# SuperAli.net
KiCad netlist of a schematic drawn in EAGLE
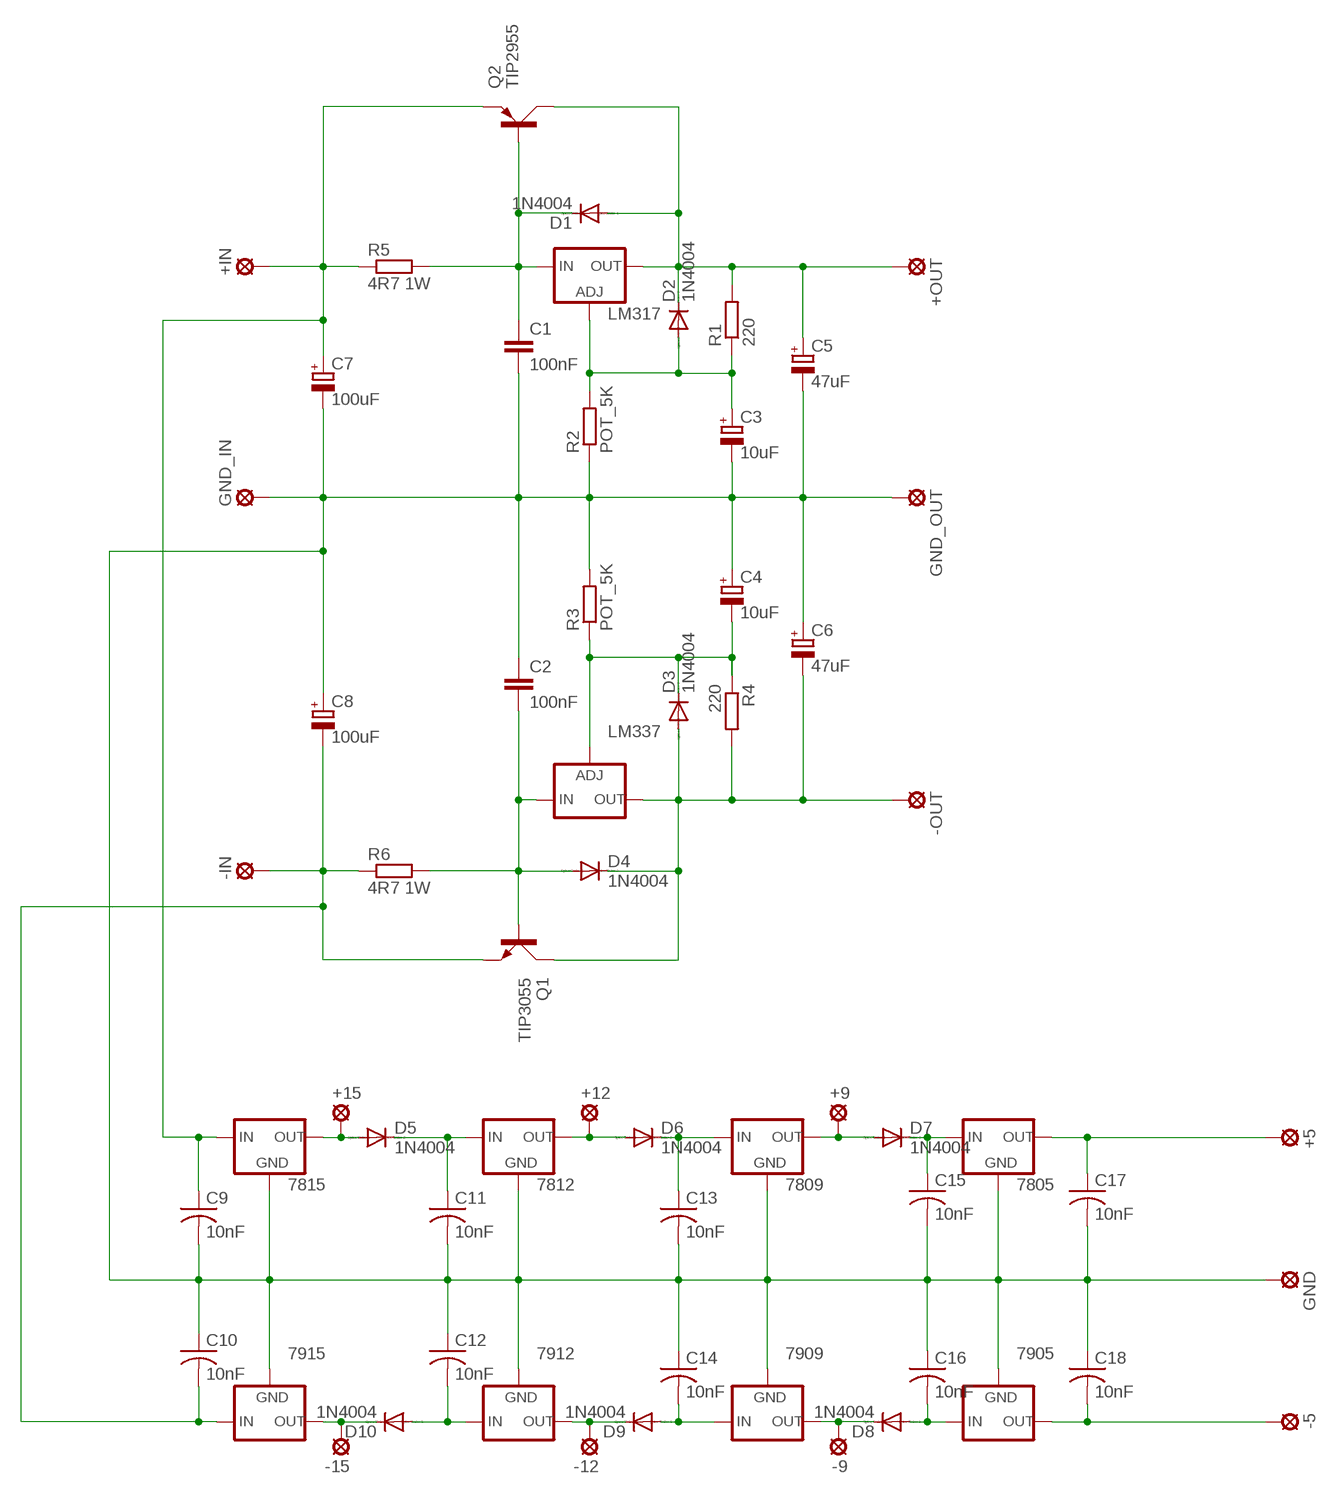
[diagram p0: schematic, sheet 1]

(export (version "E")
  (design (tool "Eeschema 10.0.6"))
  (components
    (comp (ref "+5")
      (value "LSP10")
      (footprint "eagle-import:LSP10")
      (libsource (lib "eagle-import") (part "LSP10"))
    )
    (comp (ref "+9")
      (value "LSP10")
      (footprint "eagle-import:LSP10")
      (libsource (lib "eagle-import") (part "LSP10"))
    )
    (comp (ref "+12")
      (value "LSP10")
      (footprint "eagle-import:LSP10")
      (libsource (lib "eagle-import") (part "LSP10"))
    )
    (comp (ref "+15")
      (value "LSP10")
      (footprint "eagle-import:LSP10")
      (libsource (lib "eagle-import") (part "LSP10"))
    )
    (comp (ref "+IN")
      (value "LSP13")
      (footprint "eagle-import:LSP13")
      (libsource (lib "eagle-import") (part "LSP13"))
    )
    (comp (ref "+OUT")
      (value "LSP13")
      (footprint "eagle-import:LSP13")
      (libsource (lib "eagle-import") (part "LSP13"))
    )
    (comp (ref "-5")
      (value "LSP10")
      (footprint "eagle-import:LSP10")
      (libsource (lib "eagle-import") (part "LSP10"))
    )
    (comp (ref "-9")
      (value "LSP10")
      (footprint "eagle-import:LSP10")
      (libsource (lib "eagle-import") (part "LSP10"))
    )
    (comp (ref "-12")
      (value "LSP10")
      (footprint "eagle-import:LSP10")
      (libsource (lib "eagle-import") (part "LSP10"))
    )
    (comp (ref "-15")
      (value "LSP10")
      (footprint "eagle-import:LSP10")
      (libsource (lib "eagle-import") (part "LSP10"))
    )
    (comp (ref "-IN")
      (value "LSP13")
      (footprint "eagle-import:LSP13")
      (libsource (lib "eagle-import") (part "LSP13"))
    )
    (comp (ref "-OUT")
      (value "LSP13")
      (footprint "eagle-import:LSP13")
      (libsource (lib "eagle-import") (part "LSP13"))
    )
    (comp (ref "7805")
      (value "78XXS")
      (footprint "eagle-import:78XXS")
      (libsource (lib "eagle-import") (part "78XXS"))
    )
    (comp (ref "7809")
      (value "78XXS")
      (footprint "eagle-import:78XXS")
      (libsource (lib "eagle-import") (part "78XXS"))
    )
    (comp (ref "7812")
      (value "78XXS")
      (footprint "eagle-import:78XXS")
      (libsource (lib "eagle-import") (part "78XXS"))
    )
    (comp (ref "7815")
      (value "78XXS")
      (footprint "eagle-import:78XXS")
      (libsource (lib "eagle-import") (part "78XXS"))
    )
    (comp (ref "7905")
      (value "79XXS")
      (footprint "eagle-import:79XXS")
      (libsource (lib "eagle-import") (part "79XXS"))
    )
    (comp (ref "7909")
      (value "79XXS")
      (footprint "eagle-import:79XXS")
      (libsource (lib "eagle-import") (part "79XXS"))
    )
    (comp (ref "7912")
      (value "79XXS")
      (footprint "eagle-import:79XXS")
      (libsource (lib "eagle-import") (part "79XXS"))
    )
    (comp (ref "7915")
      (value "79XXS")
      (footprint "eagle-import:79XXS")
      (libsource (lib "eagle-import") (part "79XXS"))
    )
    (comp (ref "C1")
      (value "100nF")
      (footprint "eagle-import:C025-040X050")
      (libsource (lib "eagle-import") (part "C-EU025-040X050"))
    )
    (comp (ref "C2")
      (value "100nF")
      (footprint "eagle-import:C025-040X050")
      (libsource (lib "eagle-import") (part "C-EU025-040X050"))
    )
    (comp (ref "C3")
      (value "10uF")
      (footprint "eagle-import:E2-5")
      (libsource (lib "eagle-import") (part "CPOL-EUE2-5"))
    )
    (comp (ref "C4")
      (value "10uF")
      (footprint "eagle-import:E2-5")
      (libsource (lib "eagle-import") (part "CPOL-EUE2-5"))
    )
    (comp (ref "C5")
      (value "47uF")
      (footprint "eagle-import:E3,5-10")
      (libsource (lib "eagle-import") (part "CPOL-EUE3.5-10"))
    )
    (comp (ref "C6")
      (value "47uF")
      (footprint "eagle-import:E3,5-10")
      (libsource (lib "eagle-import") (part "CPOL-EUE3.5-10"))
    )
    (comp (ref "C7")
      (value "100uF")
      (footprint "eagle-import:E7,5-16")
      (libsource (lib "eagle-import") (part "CPOL-EUE7.5-16"))
    )
    (comp (ref "C8")
      (value "100uF")
      (footprint "eagle-import:E7,5-16")
      (libsource (lib "eagle-import") (part "CPOL-EUE7.5-16"))
    )
    (comp (ref "C9")
      (value "10nF")
      (footprint "eagle-import:C025-025X050")
      (libsource (lib "eagle-import") (part "C-US025-025X050"))
    )
    (comp (ref "C10")
      (value "10nF")
      (footprint "eagle-import:C025-025X050")
      (libsource (lib "eagle-import") (part "C-US025-025X050"))
    )
    (comp (ref "C11")
      (value "10nF")
      (footprint "eagle-import:C025-025X050")
      (libsource (lib "eagle-import") (part "C-US025-025X050"))
    )
    (comp (ref "C12")
      (value "10nF")
      (footprint "eagle-import:C025-025X050")
      (libsource (lib "eagle-import") (part "C-US025-025X050"))
    )
    (comp (ref "C13")
      (value "10nF")
      (footprint "eagle-import:C025-025X050")
      (libsource (lib "eagle-import") (part "C-US025-025X050"))
    )
    (comp (ref "C14")
      (value "10nF")
      (footprint "eagle-import:C025-025X050")
      (libsource (lib "eagle-import") (part "C-US025-025X050"))
    )
    (comp (ref "C15")
      (value "10nF")
      (footprint "eagle-import:C025-025X050")
      (libsource (lib "eagle-import") (part "C-US025-025X050"))
    )
    (comp (ref "C16")
      (value "10nF")
      (footprint "eagle-import:C025-025X050")
      (libsource (lib "eagle-import") (part "C-US025-025X050"))
    )
    (comp (ref "C17")
      (value "10nF")
      (footprint "eagle-import:C025-025X050")
      (libsource (lib "eagle-import") (part "C-US025-025X050"))
    )
    (comp (ref "C18")
      (value "10nF")
      (footprint "eagle-import:C025-025X050")
      (libsource (lib "eagle-import") (part "C-US025-025X050"))
    )
    (comp (ref "D1")
      (value "1N4004")
      (footprint "eagle-import:DO41-10")
      (libsource (lib "eagle-import") (part "1N4004"))
    )
    (comp (ref "D2")
      (value "1N4004")
      (footprint "eagle-import:DO41-10")
      (libsource (lib "eagle-import") (part "1N4004"))
    )
    (comp (ref "D3")
      (value "1N4004")
      (footprint "eagle-import:DO41-10")
      (libsource (lib "eagle-import") (part "1N4004"))
    )
    (comp (ref "D4")
      (value "1N4004")
      (footprint "eagle-import:DO41-10")
      (libsource (lib "eagle-import") (part "1N4004"))
    )
    (comp (ref "D5")
      (value "1N4004")
      (footprint "eagle-import:DO41-10")
      (libsource (lib "eagle-import") (part "1N4004"))
    )
    (comp (ref "D6")
      (value "1N4004")
      (footprint "eagle-import:DO41-10")
      (libsource (lib "eagle-import") (part "1N4004"))
    )
    (comp (ref "D7")
      (value "1N4004")
      (footprint "eagle-import:DO41-10")
      (libsource (lib "eagle-import") (part "1N4004"))
    )
    (comp (ref "D8")
      (value "1N4004")
      (footprint "eagle-import:DO41-10")
      (libsource (lib "eagle-import") (part "1N4004"))
    )
    (comp (ref "D9")
      (value "1N4004")
      (footprint "eagle-import:DO41-10")
      (libsource (lib "eagle-import") (part "1N4004"))
    )
    (comp (ref "D10")
      (value "1N4004")
      (footprint "eagle-import:DO41-10")
      (libsource (lib "eagle-import") (part "1N4004"))
    )
    (comp (ref "GND")
      (value "LSP10")
      (footprint "eagle-import:LSP10")
      (libsource (lib "eagle-import") (part "LSP10"))
    )
    (comp (ref "GND_IN")
      (value "LSP13")
      (footprint "eagle-import:LSP13")
      (libsource (lib "eagle-import") (part "LSP13"))
    )
    (comp (ref "GND_OUT")
      (value "LSP13")
      (footprint "eagle-import:LSP13")
      (libsource (lib "eagle-import") (part "LSP13"))
    )
    (comp (ref "LM317")
      (value "LM317TS")
      (footprint "eagle-import:317TS")
      (libsource (lib "eagle-import") (part "LM317TS"))
    )
    (comp (ref "LM337")
      (value "LM337TS")
      (footprint "eagle-import:337TS")
      (libsource (lib "eagle-import") (part "LM337TS"))
    )
    (comp (ref "Q1")
      (value "TIP3055")
      (footprint "eagle-import:TOP3AV")
      (libsource (lib "eagle-import") (part "TIP3055"))
    )
    (comp (ref "Q2")
      (value "TIP2955")
      (footprint "eagle-import:TOP3AV")
      (libsource (lib "eagle-import") (part "TIP2955"))
    )
    (comp (ref "R1")
      (value "220")
      (footprint "eagle-import:0207_7")
      (libsource (lib "eagle-import") (part "R-EU_0207/7"))
    )
    (comp (ref "R2")
      (value "POT_5K")
      (footprint "eagle-import:0207_7")
      (libsource (lib "eagle-import") (part "R-EU_0207/7"))
    )
    (comp (ref "R3")
      (value "POT_5K")
      (footprint "eagle-import:0207_7")
      (libsource (lib "eagle-import") (part "R-EU_0207/7"))
    )
    (comp (ref "R4")
      (value "220")
      (footprint "eagle-import:0207_7")
      (libsource (lib "eagle-import") (part "R-EU_0207/7"))
    )
    (comp (ref "R5")
      (value "4R7 1W")
      (footprint "eagle-import:0617_17")
      (libsource (lib "eagle-import") (part "R-EU_0617/17"))
    )
    (comp (ref "R6")
      (value "4R7 1W")
      (footprint "eagle-import:0617_17")
      (libsource (lib "eagle-import") (part "R-EU_0617/17"))
    )
  )
  (nets
    (net (code "1") (name "Net-(+5-PadMP)") (class "Default")
      (node (ref "+5") (pin "MP") (pinfunction "MP_MP") (pintype "passive"))
      (node (ref "7805") (pin "OUT") (pinfunction "OUT_OUT") (pintype "passive"))
      (node (ref "C17") (pin "1") (pinfunction "1_1") (pintype "passive"))
    )
    (net (code "2") (name "Net-(+9-PadMP)") (class "Default")
      (node (ref "+9") (pin "MP") (pinfunction "MP_MP") (pintype "passive"))
      (node (ref "7809") (pin "OUT") (pinfunction "OUT_OUT") (pintype "passive"))
      (node (ref "D7") (pin "A") (pinfunction "A_A") (pintype "passive"))
    )
    (net (code "3") (name "Net-(+12-PadMP)") (class "Default")
      (node (ref "+12") (pin "MP") (pinfunction "MP_MP") (pintype "passive"))
      (node (ref "7812") (pin "OUT") (pinfunction "OUT_OUT") (pintype "passive"))
      (node (ref "D6") (pin "A") (pinfunction "A_A") (pintype "passive"))
    )
    (net (code "4") (name "Net-(+15-PadMP)") (class "Default")
      (node (ref "+15") (pin "MP") (pinfunction "MP_MP") (pintype "passive"))
      (node (ref "7815") (pin "OUT") (pinfunction "OUT_OUT") (pintype "passive"))
      (node (ref "D5") (pin "A") (pinfunction "A_A") (pintype "passive"))
    )
    (net (code "5") (name "Net-(+IN-PadMP)") (class "Default")
      (node (ref "+IN") (pin "MP") (pinfunction "MP_MP") (pintype "passive"))
      (node (ref "7815") (pin "IN") (pinfunction "IN_IN") (pintype "input"))
      (node (ref "C7") (pin "+") (pinfunction "+_+") (pintype "passive"))
      (node (ref "C9") (pin "1") (pinfunction "1_1") (pintype "passive"))
      (node (ref "Q2") (pin "E") (pinfunction "E_E") (pintype "passive"))
      (node (ref "R5") (pin "1") (pinfunction "1_1") (pintype "passive"))
    )
    (net (code "6") (name "Net-(-5-PadMP)") (class "Default")
      (node (ref "-5") (pin "MP") (pinfunction "MP_MP") (pintype "passive"))
      (node (ref "7905") (pin "OUT") (pinfunction "OUT_OUT") (pintype "passive"))
      (node (ref "C18") (pin "2") (pinfunction "2_2") (pintype "passive"))
    )
    (net (code "7") (name "Net-(-9-PadMP)") (class "Default")
      (node (ref "-9") (pin "MP") (pinfunction "MP_MP") (pintype "passive"))
      (node (ref "7909") (pin "OUT") (pinfunction "OUT_OUT") (pintype "passive"))
      (node (ref "D8") (pin "C") (pinfunction "C_C") (pintype "passive"))
    )
    (net (code "8") (name "Net-(-12-PadMP)") (class "Default")
      (node (ref "-12") (pin "MP") (pinfunction "MP_MP") (pintype "passive"))
      (node (ref "7912") (pin "OUT") (pinfunction "OUT_OUT") (pintype "passive"))
      (node (ref "D9") (pin "C") (pinfunction "C_C") (pintype "passive"))
    )
    (net (code "9") (name "Net-(-15-PadMP)") (class "Default")
      (node (ref "-15") (pin "MP") (pinfunction "MP_MP") (pintype "passive"))
      (node (ref "7915") (pin "OUT") (pinfunction "OUT_OUT") (pintype "passive"))
      (node (ref "D10") (pin "C") (pinfunction "C_C") (pintype "passive"))
    )
    (net (code "10") (name "Net-(-IN-PadMP)") (class "Default")
      (node (ref "-IN") (pin "MP") (pinfunction "MP_MP") (pintype "passive"))
      (node (ref "7915") (pin "IN") (pinfunction "IN_IN") (pintype "input"))
      (node (ref "C10") (pin "2") (pinfunction "2_2") (pintype "passive"))
      (node (ref "C8") (pin "-") (pinfunction "-_-") (pintype "passive"))
      (node (ref "Q1") (pin "E") (pinfunction "E_E") (pintype "passive"))
      (node (ref "R6") (pin "1") (pinfunction "1_1") (pintype "passive"))
    )
    (net (code "11") (name "Net-(7805-PadGND)") (class "Default")
      (node (ref "7805") (pin "GND") (pinfunction "GND_GND") (pintype "input"))
      (node (ref "7809") (pin "GND") (pinfunction "GND_GND") (pintype "input"))
      (node (ref "7812") (pin "GND") (pinfunction "GND_GND") (pintype "input"))
      (node (ref "7815") (pin "GND") (pinfunction "GND_GND") (pintype "input"))
      (node (ref "7905") (pin "GND") (pinfunction "GND_GND") (pintype "input"))
      (node (ref "7909") (pin "GND") (pinfunction "GND_GND") (pintype "input"))
      (node (ref "7912") (pin "GND") (pinfunction "GND_GND") (pintype "input"))
      (node (ref "7915") (pin "GND") (pinfunction "GND_GND") (pintype "input"))
      (node (ref "C1") (pin "2") (pinfunction "2_2") (pintype "passive"))
      (node (ref "C10") (pin "1") (pinfunction "1_1") (pintype "passive"))
      (node (ref "C11") (pin "2") (pinfunction "2_2") (pintype "passive"))
      (node (ref "C12") (pin "1") (pinfunction "1_1") (pintype "passive"))
      (node (ref "C13") (pin "2") (pinfunction "2_2") (pintype "passive"))
      (node (ref "C14") (pin "1") (pinfunction "1_1") (pintype "passive"))
      (node (ref "C15") (pin "2") (pinfunction "2_2") (pintype "passive"))
      (node (ref "C16") (pin "1") (pinfunction "1_1") (pintype "passive"))
      (node (ref "C17") (pin "2") (pinfunction "2_2") (pintype "passive"))
      (node (ref "C18") (pin "1") (pinfunction "1_1") (pintype "passive"))
      (node (ref "C2") (pin "1") (pinfunction "1_1") (pintype "passive"))
      (node (ref "C3") (pin "-") (pinfunction "-_-") (pintype "passive"))
      (node (ref "C4") (pin "+") (pinfunction "+_+") (pintype "passive"))
      (node (ref "C5") (pin "-") (pinfunction "-_-") (pintype "passive"))
      (node (ref "C6") (pin "+") (pinfunction "+_+") (pintype "passive"))
      (node (ref "C7") (pin "-") (pinfunction "-_-") (pintype "passive"))
      (node (ref "C8") (pin "+") (pinfunction "+_+") (pintype "passive"))
      (node (ref "C9") (pin "2") (pinfunction "2_2") (pintype "passive"))
      (node (ref "GND") (pin "MP") (pinfunction "MP_MP") (pintype "passive"))
      (node (ref "GND_IN") (pin "MP") (pinfunction "MP_MP") (pintype "passive"))
      (node (ref "GND_OUT") (pin "MP") (pinfunction "MP_MP") (pintype "passive"))
      (node (ref "R2") (pin "1") (pinfunction "1_1") (pintype "passive"))
      (node (ref "R3") (pin "2") (pinfunction "2_2") (pintype "passive"))
    )
    (net (code "12") (name "Net-(7805-PadIN)") (class "Default")
      (node (ref "7805") (pin "IN") (pinfunction "IN_IN") (pintype "input"))
      (node (ref "C15") (pin "1") (pinfunction "1_1") (pintype "passive"))
      (node (ref "D7") (pin "C") (pinfunction "C_C") (pintype "passive"))
    )
    (net (code "13") (name "Net-(7809-PadIN)") (class "Default")
      (node (ref "7809") (pin "IN") (pinfunction "IN_IN") (pintype "input"))
      (node (ref "C13") (pin "1") (pinfunction "1_1") (pintype "passive"))
      (node (ref "D6") (pin "C") (pinfunction "C_C") (pintype "passive"))
    )
    (net (code "14") (name "Net-(7812-PadIN)") (class "Default")
      (node (ref "7812") (pin "IN") (pinfunction "IN_IN") (pintype "input"))
      (node (ref "C11") (pin "1") (pinfunction "1_1") (pintype "passive"))
      (node (ref "D5") (pin "C") (pinfunction "C_C") (pintype "passive"))
    )
    (net (code "15") (name "Net-(7905-PadIN)") (class "Default")
      (node (ref "7905") (pin "IN") (pinfunction "IN_IN") (pintype "input"))
      (node (ref "C16") (pin "2") (pinfunction "2_2") (pintype "passive"))
      (node (ref "D8") (pin "A") (pinfunction "A_A") (pintype "passive"))
    )
    (net (code "16") (name "Net-(7909-PadIN)") (class "Default")
      (node (ref "7909") (pin "IN") (pinfunction "IN_IN") (pintype "input"))
      (node (ref "C14") (pin "2") (pinfunction "2_2") (pintype "passive"))
      (node (ref "D9") (pin "A") (pinfunction "A_A") (pintype "passive"))
    )
    (net (code "17") (name "Net-(7912-PadIN)") (class "Default")
      (node (ref "7912") (pin "IN") (pinfunction "IN_IN") (pintype "input"))
      (node (ref "C12") (pin "2") (pinfunction "2_2") (pintype "passive"))
      (node (ref "D10") (pin "A") (pinfunction "A_A") (pintype "passive"))
    )
    (net (code "18") (name "Net-(LM317-ADJ)") (class "Default")
      (node (ref "C3") (pin "+") (pinfunction "+_+") (pintype "passive"))
      (node (ref "D2") (pin "A") (pinfunction "A_A") (pintype "passive"))
      (node (ref "LM317") (pin "1") (pinfunction "ADJ_1") (pintype "input"))
      (node (ref "R1") (pin "1") (pinfunction "1_1") (pintype "passive"))
      (node (ref "R2") (pin "2") (pinfunction "2_2") (pintype "passive"))
    )
    (net (code "19") (name "Net-(LM317-IN)") (class "Default")
      (node (ref "C1") (pin "1") (pinfunction "1_1") (pintype "passive"))
      (node (ref "D1") (pin "C") (pinfunction "C_C") (pintype "passive"))
      (node (ref "LM317") (pin "3") (pinfunction "IN_3") (pintype "input"))
      (node (ref "Q2") (pin "B") (pinfunction "B_B") (pintype "passive"))
      (node (ref "R5") (pin "2") (pinfunction "2_2") (pintype "passive"))
    )
    (net (code "20") (name "Net-(LM317-OUT)") (class "Default")
      (node (ref "+OUT") (pin "MP") (pinfunction "MP_MP") (pintype "passive"))
      (node (ref "C5") (pin "+") (pinfunction "+_+") (pintype "passive"))
      (node (ref "D1") (pin "A") (pinfunction "A_A") (pintype "passive"))
      (node (ref "D2") (pin "C") (pinfunction "C_C") (pintype "passive"))
      (node (ref "LM317") (pin "2") (pinfunction "OUT_2") (pintype "passive"))
      (node (ref "Q2") (pin "C") (pinfunction "C_C") (pintype "passive"))
      (node (ref "R1") (pin "2") (pinfunction "2_2") (pintype "passive"))
    )
    (net (code "21") (name "Net-(LM337-ADJ)") (class "Default")
      (node (ref "C4") (pin "-") (pinfunction "-_-") (pintype "passive"))
      (node (ref "D3") (pin "C") (pinfunction "C_C") (pintype "passive"))
      (node (ref "LM337") (pin "1") (pinfunction "ADJ_1") (pintype "input"))
      (node (ref "R3") (pin "1") (pinfunction "1_1") (pintype "passive"))
      (node (ref "R4") (pin "1") (pinfunction "1_1") (pintype "passive"))
    )
    (net (code "22") (name "Net-(LM337-IN)") (class "Default")
      (node (ref "C2") (pin "2") (pinfunction "2_2") (pintype "passive"))
      (node (ref "D4") (pin "A") (pinfunction "A_A") (pintype "passive"))
      (node (ref "LM337") (pin "2") (pinfunction "IN_2") (pintype "input"))
      (node (ref "Q1") (pin "B") (pinfunction "B_B") (pintype "passive"))
      (node (ref "R6") (pin "2") (pinfunction "2_2") (pintype "passive"))
    )
    (net (code "23") (name "Net-(LM337-OUT)") (class "Default")
      (node (ref "-OUT") (pin "MP") (pinfunction "MP_MP") (pintype "passive"))
      (node (ref "C6") (pin "-") (pinfunction "-_-") (pintype "passive"))
      (node (ref "D3") (pin "A") (pinfunction "A_A") (pintype "passive"))
      (node (ref "D4") (pin "C") (pinfunction "C_C") (pintype "passive"))
      (node (ref "LM337") (pin "3") (pinfunction "OUT_3") (pintype "passive"))
      (node (ref "Q1") (pin "C") (pinfunction "C_C") (pintype "passive"))
      (node (ref "R4") (pin "2") (pinfunction "2_2") (pintype "passive"))
    )
  )
)
